# batt_rev_1.net
KiCad netlist of a schematic drawn in EAGLE
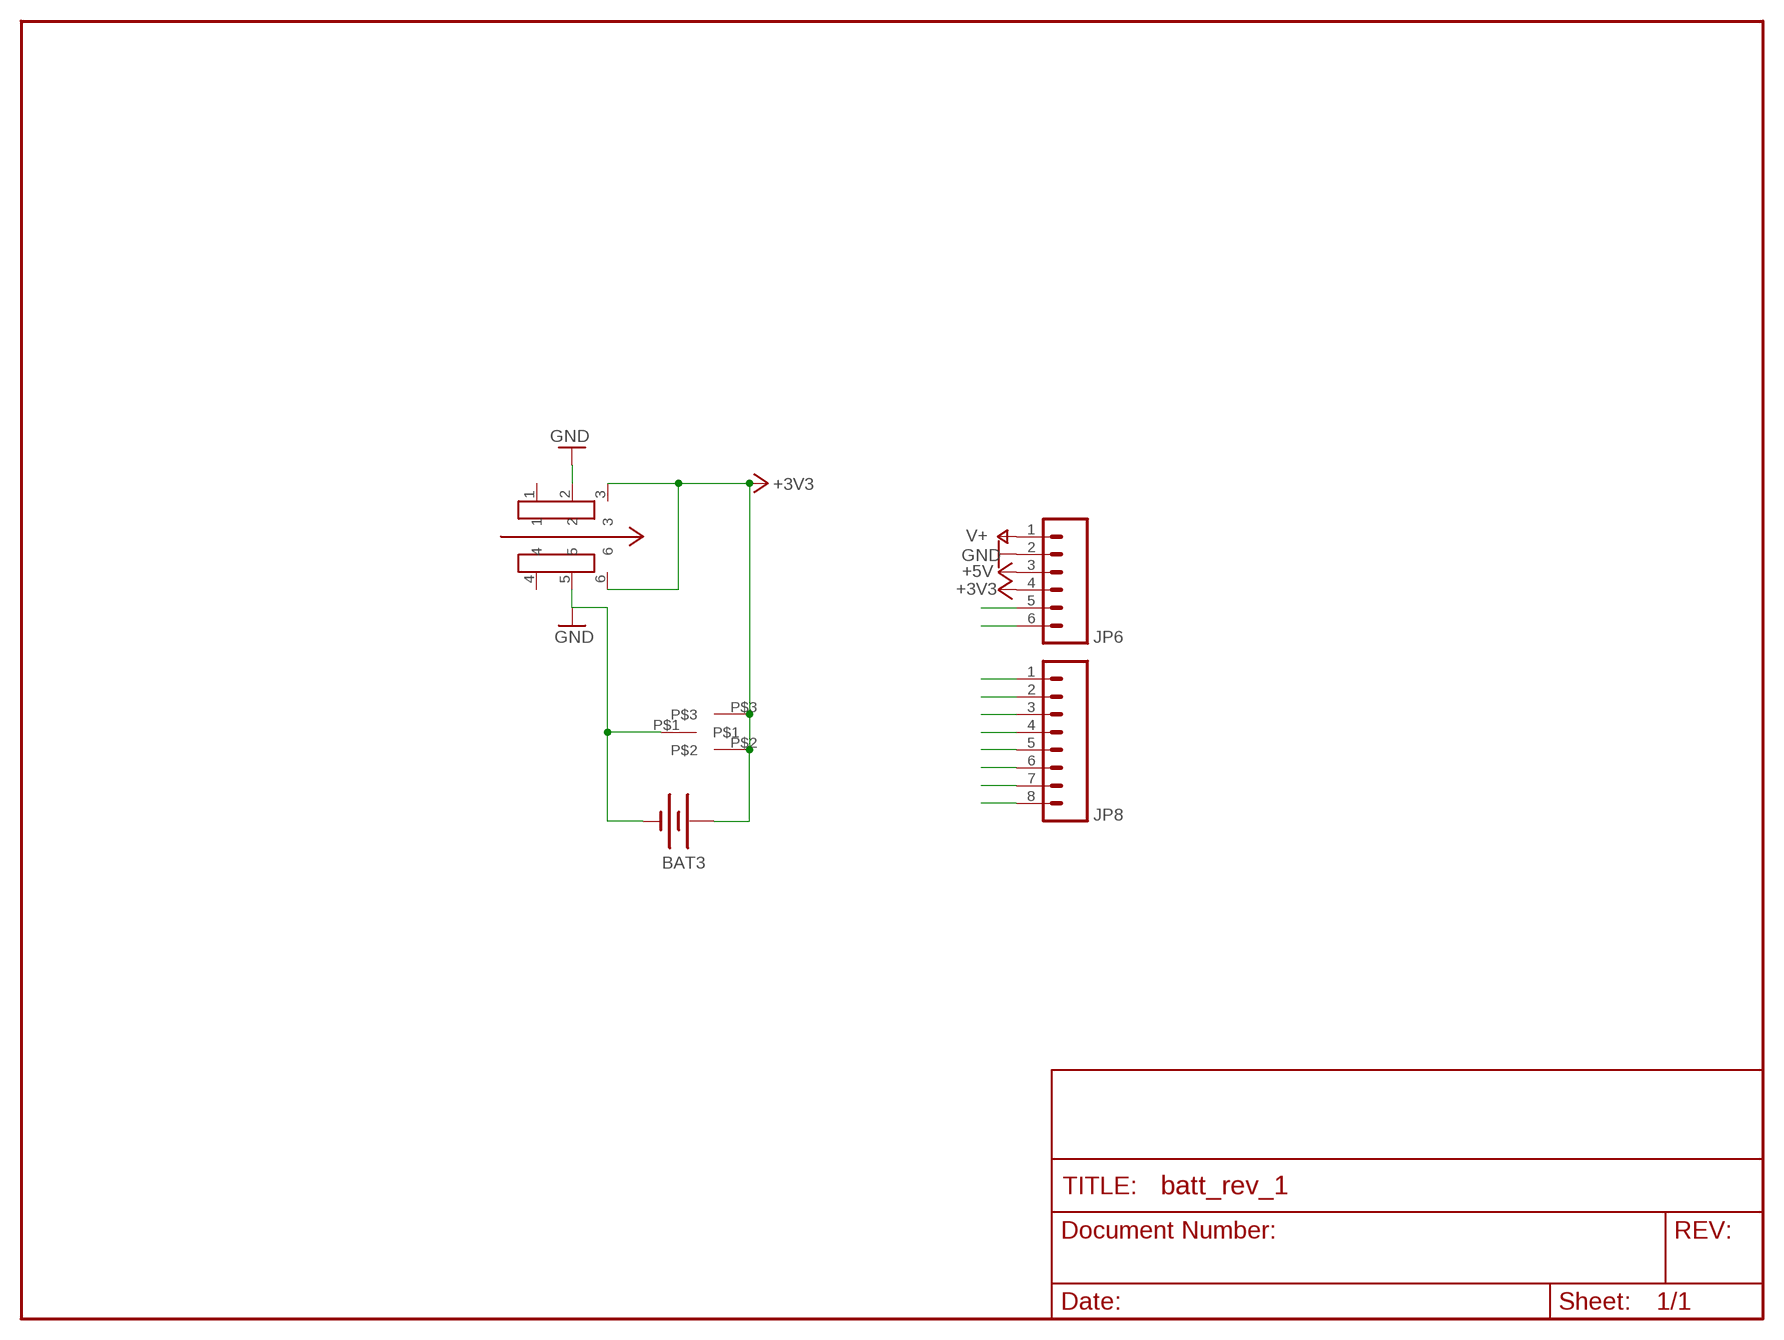
[diagram p0: schematic, sheet 1]

(export (version "E")
  (design (tool "Eeschema 10.0.6"))
  (components
    (comp (ref "BAT3")
      (value "BATTERY20PTH")
      (footprint "eagle-import:BATTCOM_20MM_PTH")
      (libsource (lib "eagle-import") (part "BATTERY20PTH"))
    )
    (comp (ref "JP6")
      (value "6")
      (footprint "eagle-import:1X06")
      (libsource (lib "eagle-import") (part "M06SIP"))
    )
    (comp (ref "JP8")
      (value "8")
      (footprint "eagle-import:1X08")
      (libsource (lib "eagle-import") (part "M081X08"))
    )
    (comp (ref "U$1")
      (value "SWITCH")
      (footprint "eagle-import:SWITCH")
      (libsource (lib "eagle-import") (part "SWITCH"))
    )
    (comp (ref "U$2")
      (value "BATT_2032")
      (footprint "eagle-import:BATT_2032")
      (libsource (lib "eagle-import") (part "BATT_2032"))
    )
  )
  (nets
    (net (code "1") (name "+3V3") (class "Default")
      (node (ref "BAT3") (pin "1") (pinfunction "+_1") (pintype "power_in"))
      (node (ref "JP6") (pin "4") (pinfunction "4_4") (pintype "passive"))
      (node (ref "U$1") (pin "3") (pinfunction "3_3") (pintype "bidirectional"))
      (node (ref "U$1") (pin "6") (pinfunction "6_6") (pintype "bidirectional"))
      (node (ref "U$2") (pin "P$2") (pinfunction "P$2_P$2") (pintype "bidirectional"))
      (node (ref "U$2") (pin "P$3") (pinfunction "P$3_P$3") (pintype "bidirectional"))
    )
    (net (code "2") (name "+5V") (class "Default")
      (node (ref "JP6") (pin "3") (pinfunction "3_3") (pintype "passive"))
    )
    (net (code "3") (name "GND") (class "Default")
      (node (ref "BAT3") (pin "2") (pinfunction "-_2") (pintype "power_in"))
      (node (ref "JP6") (pin "2") (pinfunction "2_2") (pintype "passive"))
      (node (ref "U$1") (pin "2") (pinfunction "2_2") (pintype "bidirectional"))
      (node (ref "U$1") (pin "5") (pinfunction "5_5") (pintype "bidirectional"))
      (node (ref "U$2") (pin "P$1") (pinfunction "P$1_P$1") (pintype "bidirectional"))
    )
    (net (code "4") (name "V+") (class "Default")
      (node (ref "JP6") (pin "1") (pinfunction "1_1") (pintype "passive"))
    )
    (net (code "5") (name "unconnected-(JP6-Pad5)") (class "Default")
      (node (ref "JP6") (pin "5") (pinfunction "5_5") (pintype "passive"))
    )
    (net (code "6") (name "unconnected-(JP6-Pad6)") (class "Default")
      (node (ref "JP6") (pin "6") (pinfunction "6_6") (pintype "passive"))
    )
    (net (code "7") (name "unconnected-(JP8-Pad1)") (class "Default")
      (node (ref "JP8") (pin "1") (pinfunction "1_1") (pintype "passive"))
    )
    (net (code "8") (name "unconnected-(JP8-Pad2)") (class "Default")
      (node (ref "JP8") (pin "2") (pinfunction "2_2") (pintype "passive"))
    )
    (net (code "9") (name "unconnected-(JP8-Pad3)") (class "Default")
      (node (ref "JP8") (pin "3") (pinfunction "3_3") (pintype "passive"))
    )
    (net (code "10") (name "unconnected-(JP8-Pad4)") (class "Default")
      (node (ref "JP8") (pin "4") (pinfunction "4_4") (pintype "passive"))
    )
    (net (code "11") (name "unconnected-(JP8-Pad5)") (class "Default")
      (node (ref "JP8") (pin "5") (pinfunction "5_5") (pintype "passive"))
    )
    (net (code "12") (name "unconnected-(JP8-Pad6)") (class "Default")
      (node (ref "JP8") (pin "6") (pinfunction "6_6") (pintype "passive"))
    )
    (net (code "13") (name "unconnected-(JP8-Pad7)") (class "Default")
      (node (ref "JP8") (pin "7") (pinfunction "7_7") (pintype "passive"))
    )
    (net (code "14") (name "unconnected-(JP8-Pad8)") (class "Default")
      (node (ref "JP8") (pin "8") (pinfunction "8_8") (pintype "passive"))
    )
    (net (code "15") (name "unconnected-(U$1-Pad1)") (class "Default")
      (node (ref "U$1") (pin "1") (pinfunction "1_1") (pintype "bidirectional"))
    )
    (net (code "16") (name "unconnected-(U$1-Pad4)") (class "Default")
      (node (ref "U$1") (pin "4") (pinfunction "4_4") (pintype "bidirectional"))
    )
  )
)
